# usb-dip-switch-socketed.net
KiCad netlist of a schematic drawn in EAGLE
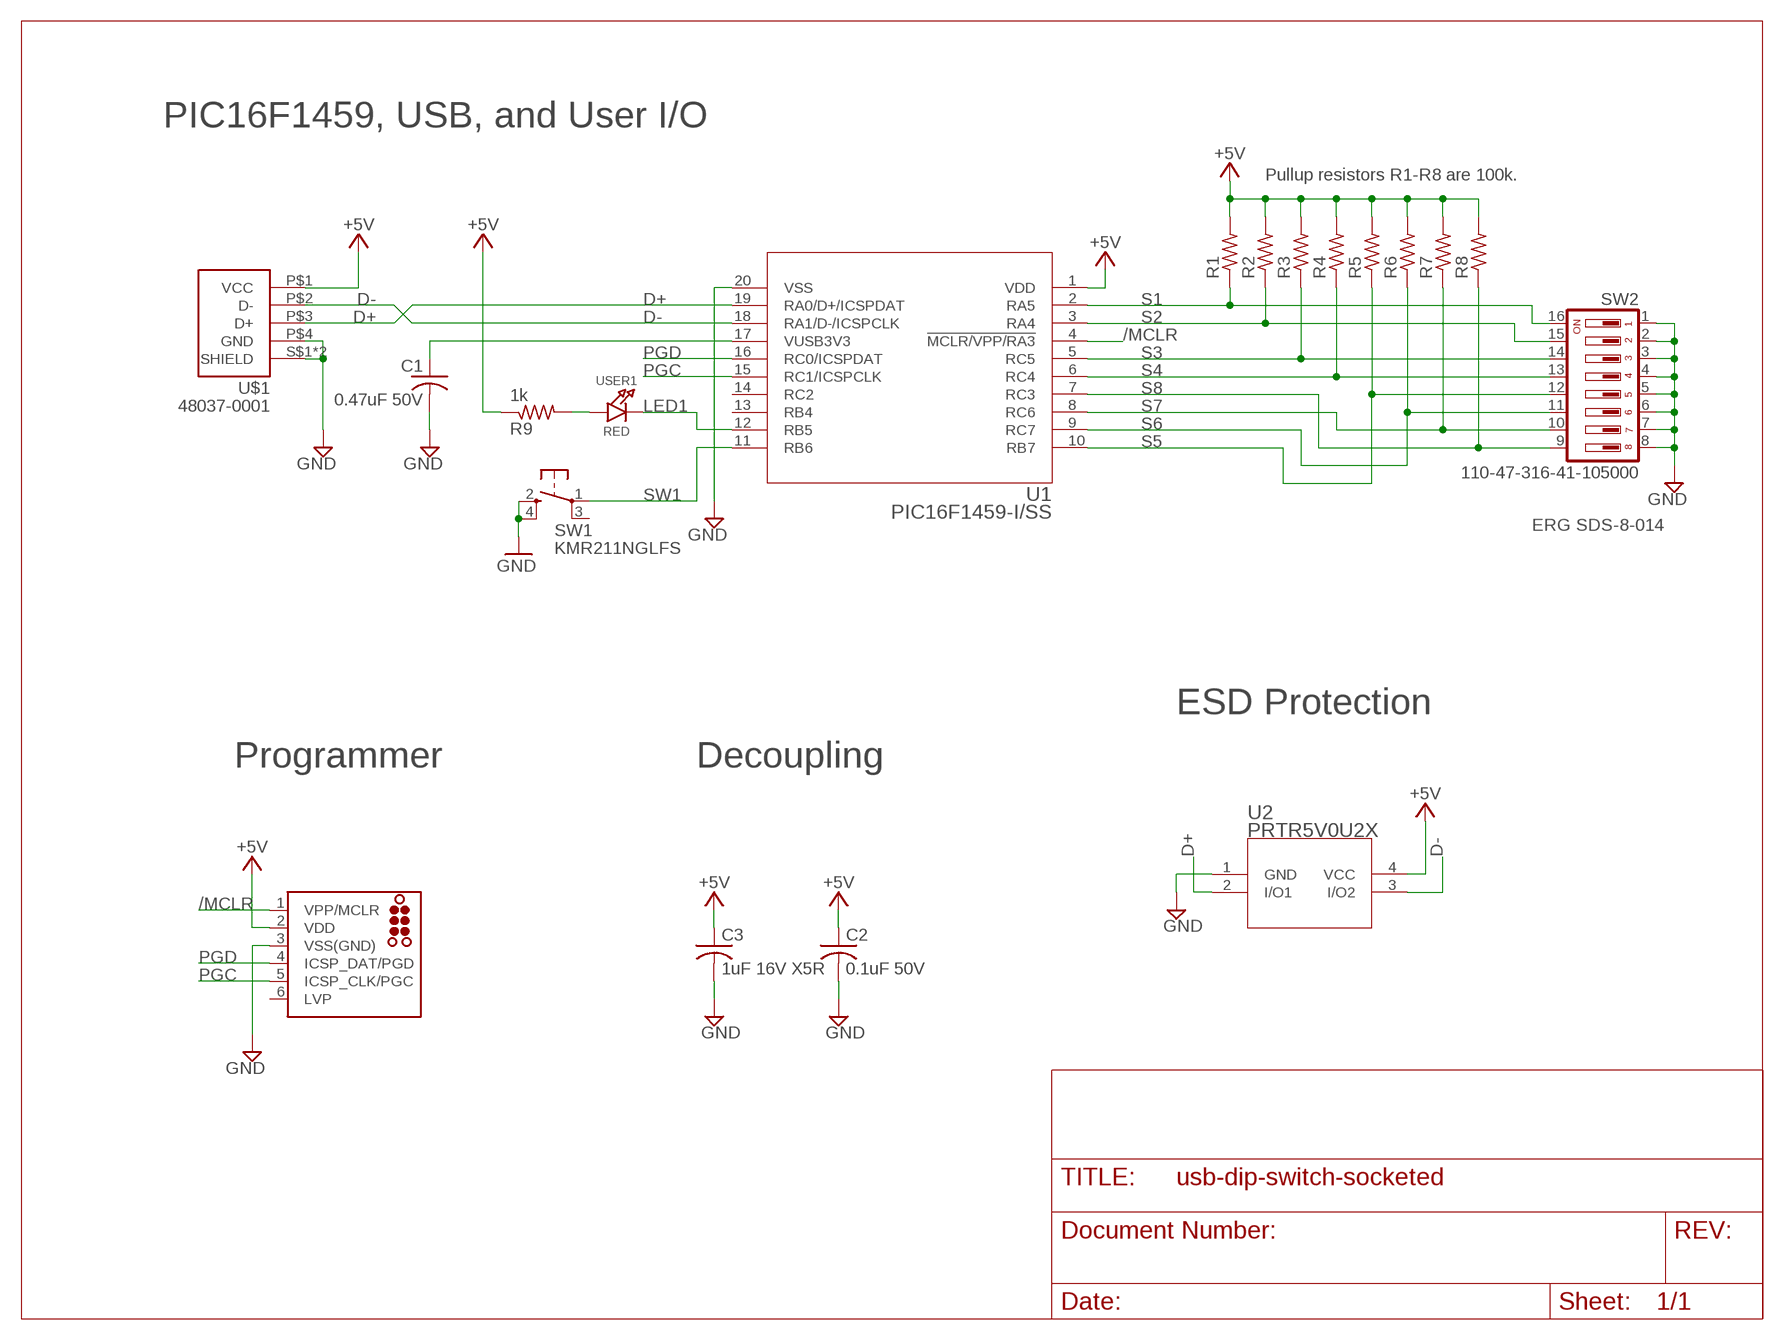
[diagram p0: schematic, sheet 1]

(export (version "E")
  (design (tool "Eeschema 10.0.6"))
  (components
    (comp (ref "C1")
      (value "0.47uF 50V")
      (footprint "eagle-import:C1206K")
      (fields (field (name "MFR") "KEMET") (field (name "MFR_PART_NO") "C1206C474K5RACTU"))
      (libsource (lib "eagle-import") (part "C-USC1206K"))
    )
    (comp (ref "C2")
      (value "0.1uF 50V")
      (footprint "eagle-import:C0603")
      (fields (field (name "MFR") "KEMET") (field (name "MFR_PART_NO") "C1206S104M5RACTU"))
      (libsource (lib "eagle-import") (part "C-USC0603"))
    )
    (comp (ref "C3")
      (value "1uF 16V X5R")
      (footprint "eagle-import:C0603")
      (fields (field (name "MFR") "KEMET") (field (name "MFR_PART_NO") "C1210C105K4PACTU"))
      (libsource (lib "eagle-import") (part "C-USC0603"))
    )
    (comp (ref "J3")
      (value "TC2030-MCP-NL")
      (footprint "eagle-import:TC2030-MCP-NL")
      (libsource (lib "eagle-import") (part "TC2030-MCP-NL"))
    )
    (comp (ref "R1")
      (value "100k")
      (footprint "eagle-import:R0603")
      (libsource (lib "eagle-import") (part "R-US_R0603"))
    )
    (comp (ref "R2")
      (value "100k")
      (footprint "eagle-import:R0603")
      (libsource (lib "eagle-import") (part "R-US_R0603"))
    )
    (comp (ref "R3")
      (value "100k")
      (footprint "eagle-import:R0603")
      (libsource (lib "eagle-import") (part "R-US_R0603"))
    )
    (comp (ref "R4")
      (value "100k")
      (footprint "eagle-import:R0603")
      (libsource (lib "eagle-import") (part "R-US_R0603"))
    )
    (comp (ref "R5")
      (value "100k")
      (footprint "eagle-import:R0603")
      (libsource (lib "eagle-import") (part "R-US_R0603"))
    )
    (comp (ref "R6")
      (value "100k")
      (footprint "eagle-import:R0603")
      (libsource (lib "eagle-import") (part "R-US_R0603"))
    )
    (comp (ref "R7")
      (value "100k")
      (footprint "eagle-import:R0603")
      (libsource (lib "eagle-import") (part "R-US_R0603"))
    )
    (comp (ref "R8")
      (value "100k")
      (footprint "eagle-import:R0603")
      (libsource (lib "eagle-import") (part "R-US_R0603"))
    )
    (comp (ref "R9")
      (value "1k")
      (footprint "eagle-import:R0805")
      (libsource (lib "eagle-import") (part "R-US_R0805"))
    )
    (comp (ref "SW1")
      (value "KMR211NGLFS")
      (footprint "eagle-import:KMR2")
      (libsource (lib "eagle-import") (part "SPST_TACT-KMR2"))
    )
    (comp (ref "SW2")
      (value "110-47-316-41-105000")
      (footprint "eagle-import:110-47-316-41-105000")
      (libsource (lib "eagle-import") (part "110-47-316-41-105000"))
    )
    (comp (ref "U$1")
      (value "48037-0001")
      (footprint "eagle-import:48037-0001")
      (libsource (lib "eagle-import") (part "48037-0001"))
    )
    (comp (ref "U1")
      (value "PIC16F1459-I/SS")
      (footprint "eagle-import:SSOP20_MC")
      (fields (field (name "MANUFACTURER_PART_NUMBER") "PIC16F1459ISS"))
      (libsource (lib "eagle-import") (part "PIC16F1459-I/SS"))
    )
    (comp (ref "U2")
      (value "PRTR5V0U2X")
      (footprint "eagle-import:SOT143B")
      (libsource (lib "eagle-import") (part "PRTR5V0U2X"))
    )
    (comp (ref "USER1")
      (value "RED")
      (footprint "eagle-import:CHIPLED_0805_NOOUTLINE")
      (libsource (lib "eagle-import") (part "LED0805_NOOUTLINE"))
    )
  )
  (nets
    (net (code "1") (name "+5V") (class "Default")
      (node (ref "C2") (pin "1") (pinfunction "1_1") (pintype "passive"))
      (node (ref "C3") (pin "1") (pinfunction "1_1") (pintype "passive"))
      (node (ref "J3") (pin "2") (pinfunction "VDD_2") (pintype "power_in"))
      (node (ref "R1") (pin "2") (pinfunction "2_2") (pintype "passive"))
      (node (ref "R2") (pin "2") (pinfunction "2_2") (pintype "passive"))
      (node (ref "R3") (pin "2") (pinfunction "2_2") (pintype "passive"))
      (node (ref "R4") (pin "2") (pinfunction "2_2") (pintype "passive"))
      (node (ref "R5") (pin "2") (pinfunction "2_2") (pintype "passive"))
      (node (ref "R6") (pin "2") (pinfunction "2_2") (pintype "passive"))
      (node (ref "R7") (pin "2") (pinfunction "2_2") (pintype "passive"))
      (node (ref "R8") (pin "2") (pinfunction "2_2") (pintype "passive"))
      (node (ref "R9") (pin "1") (pinfunction "1_1") (pintype "passive"))
      (node (ref "U$1") (pin "P$1") (pinfunction "VCC_P$1") (pintype "bidirectional"))
      (node (ref "U1") (pin "1") (pinfunction "VDD_1") (pintype "power_in"))
      (node (ref "U2") (pin "4") (pinfunction "VCC_4") (pintype "passive"))
    )
    (net (code "2") (name "/D+") (class "Default")
      (node (ref "U$1") (pin "P$3") (pinfunction "D+_P$3") (pintype "bidirectional"))
      (node (ref "U1") (pin "19") (pinfunction "RA0/D+/ICSPDAT_19") (pintype "bidirectional"))
      (node (ref "U2") (pin "2") (pinfunction "I/O1_2") (pintype "passive"))
    )
    (net (code "3") (name "/D-") (class "Default")
      (node (ref "U$1") (pin "P$2") (pinfunction "D-_P$2") (pintype "bidirectional"))
      (node (ref "U1") (pin "18") (pinfunction "RA1/D-/ICSPCLK_18") (pintype "bidirectional"))
      (node (ref "U2") (pin "3") (pinfunction "I/O2_3") (pintype "passive"))
    )
    (net (code "4") (name "/LED1") (class "Default")
      (node (ref "U1") (pin "12") (pinfunction "RB5_12") (pintype "bidirectional"))
      (node (ref "USER1") (pin "C") (pinfunction "C_C") (pintype "passive"))
    )
    (net (code "5") (name "/PGC") (class "Default")
      (node (ref "J3") (pin "5") (pinfunction "ICSP_CLK/PGC_5") (pintype "output"))
      (node (ref "U1") (pin "15") (pinfunction "RC1/ICSPCLK_15") (pintype "bidirectional"))
    )
    (net (code "6") (name "/PGD") (class "Default")
      (node (ref "J3") (pin "4") (pinfunction "ICSP_DAT/PGD_4") (pintype "bidirectional"))
      (node (ref "U1") (pin "16") (pinfunction "RC0/ICSPDAT_16") (pintype "bidirectional"))
    )
    (net (code "7") (name "/S1") (class "Default")
      (node (ref "R1") (pin "1") (pinfunction "1_1") (pintype "passive"))
      (node (ref "SW2") (pin "16") (pinfunction "16_16") (pintype "passive"))
      (node (ref "U1") (pin "2") (pinfunction "RA5_2") (pintype "bidirectional"))
    )
    (net (code "8") (name "/S2") (class "Default")
      (node (ref "R2") (pin "1") (pinfunction "1_1") (pintype "passive"))
      (node (ref "SW2") (pin "15") (pinfunction "15_15") (pintype "passive"))
      (node (ref "U1") (pin "3") (pinfunction "RA4_3") (pintype "bidirectional"))
    )
    (net (code "9") (name "/S3") (class "Default")
      (node (ref "R3") (pin "1") (pinfunction "1_1") (pintype "passive"))
      (node (ref "SW2") (pin "14") (pinfunction "14_14") (pintype "passive"))
      (node (ref "U1") (pin "5") (pinfunction "RC5_5") (pintype "bidirectional"))
    )
    (net (code "10") (name "/S4") (class "Default")
      (node (ref "R4") (pin "1") (pinfunction "1_1") (pintype "passive"))
      (node (ref "SW2") (pin "13") (pinfunction "13_13") (pintype "passive"))
      (node (ref "U1") (pin "6") (pinfunction "RC4_6") (pintype "bidirectional"))
    )
    (net (code "11") (name "/S5") (class "Default")
      (node (ref "R5") (pin "1") (pinfunction "1_1") (pintype "passive"))
      (node (ref "SW2") (pin "12") (pinfunction "12_12") (pintype "passive"))
      (node (ref "U1") (pin "10") (pinfunction "RB7_10") (pintype "bidirectional"))
    )
    (net (code "12") (name "/S6") (class "Default")
      (node (ref "R6") (pin "1") (pinfunction "1_1") (pintype "passive"))
      (node (ref "SW2") (pin "11") (pinfunction "11_11") (pintype "passive"))
      (node (ref "U1") (pin "9") (pinfunction "RC7_9") (pintype "bidirectional"))
    )
    (net (code "13") (name "/S7") (class "Default")
      (node (ref "R7") (pin "1") (pinfunction "1_1") (pintype "passive"))
      (node (ref "SW2") (pin "10") (pinfunction "10_10") (pintype "passive"))
      (node (ref "U1") (pin "8") (pinfunction "RC6_8") (pintype "bidirectional"))
    )
    (net (code "14") (name "/S8") (class "Default")
      (node (ref "R8") (pin "1") (pinfunction "1_1") (pintype "passive"))
      (node (ref "SW2") (pin "9") (pinfunction "9_9") (pintype "passive"))
      (node (ref "U1") (pin "7") (pinfunction "RC3_7") (pintype "bidirectional"))
    )
    (net (code "15") (name "/SW1") (class "Default")
      (node (ref "SW1") (pin "1") (pinfunction "P_1") (pintype "passive"))
      (node (ref "U1") (pin "11") (pinfunction "RB6_11") (pintype "bidirectional"))
    )
    (net (code "16") (name "/{slash}MCLR") (class "Default")
      (node (ref "J3") (pin "1") (pinfunction "VPP/MCLR_1") (pintype "passive"))
      (node (ref "U1") (pin "4") (pinfunction "~{MCLR/VPP/RA3}_4") (pintype "bidirectional"))
    )
    (net (code "17") (name "GND") (class "Default")
      (node (ref "C1") (pin "2") (pinfunction "2_2") (pintype "passive"))
      (node (ref "C2") (pin "2") (pinfunction "2_2") (pintype "passive"))
      (node (ref "C3") (pin "2") (pinfunction "2_2") (pintype "passive"))
      (node (ref "J3") (pin "3") (pinfunction "VSS(GND)_3") (pintype "power_in"))
      (node (ref "SW1") (pin "2") (pinfunction "S_2") (pintype "passive"))
      (node (ref "SW1") (pin "4") (pinfunction "S1_4") (pintype "passive"))
      (node (ref "SW2") (pin "1") (pinfunction "1_1") (pintype "passive"))
      (node (ref "SW2") (pin "2") (pinfunction "2_2") (pintype "passive"))
      (node (ref "SW2") (pin "3") (pinfunction "3_3") (pintype "passive"))
      (node (ref "SW2") (pin "4") (pinfunction "4_4") (pintype "passive"))
      (node (ref "SW2") (pin "5") (pinfunction "5_5") (pintype "passive"))
      (node (ref "SW2") (pin "6") (pinfunction "6_6") (pintype "passive"))
      (node (ref "SW2") (pin "7") (pinfunction "7_7") (pintype "passive"))
      (node (ref "SW2") (pin "8") (pinfunction "8_8") (pintype "passive"))
      (node (ref "U$1") (pin "P$4") (pinfunction "GND_P$4") (pintype "bidirectional"))
      (node (ref "U$1") (pin "S$1") (pinfunction "SHIELD_S$1") (pintype "bidirectional"))
      (node (ref "U$1") (pin "S$2") (pinfunction "SHIELD_S$2") (pintype "bidirectional"))
      (node (ref "U1") (pin "20") (pinfunction "VSS_20") (pintype "power_in"))
      (node (ref "U2") (pin "1") (pinfunction "GND_1") (pintype "passive"))
    )
    (net (code "18") (name "Net-(R9-Pad2)") (class "Default")
      (node (ref "R9") (pin "2") (pinfunction "2_2") (pintype "passive"))
      (node (ref "USER1") (pin "A") (pinfunction "A_A") (pintype "passive"))
    )
    (net (code "19") (name "Net-(U1-VUSB3V3)") (class "Default")
      (node (ref "C1") (pin "1") (pinfunction "1_1") (pintype "passive"))
      (node (ref "U1") (pin "17") (pinfunction "VUSB3V3_17") (pintype "power_in"))
    )
    (net (code "20") (name "unconnected-(J3-LVP-Pad6)") (class "Default")
      (node (ref "J3") (pin "6") (pinfunction "LVP_6") (pintype "bidirectional"))
    )
    (net (code "21") (name "unconnected-(SW1-P1-Pad3)") (class "Default")
      (node (ref "SW1") (pin "3") (pinfunction "P1_3") (pintype "passive"))
    )
    (net (code "22") (name "unconnected-(U1-RB4-Pad13)") (class "Default")
      (node (ref "U1") (pin "13") (pinfunction "RB4_13") (pintype "bidirectional"))
    )
    (net (code "23") (name "unconnected-(U1-RC2-Pad14)") (class "Default")
      (node (ref "U1") (pin "14") (pinfunction "RC2_14") (pintype "bidirectional"))
    )
  )
)
